# ESP_LoRa_ScaleSansotta.net
KiCad netlist of a schematic drawn in EAGLE
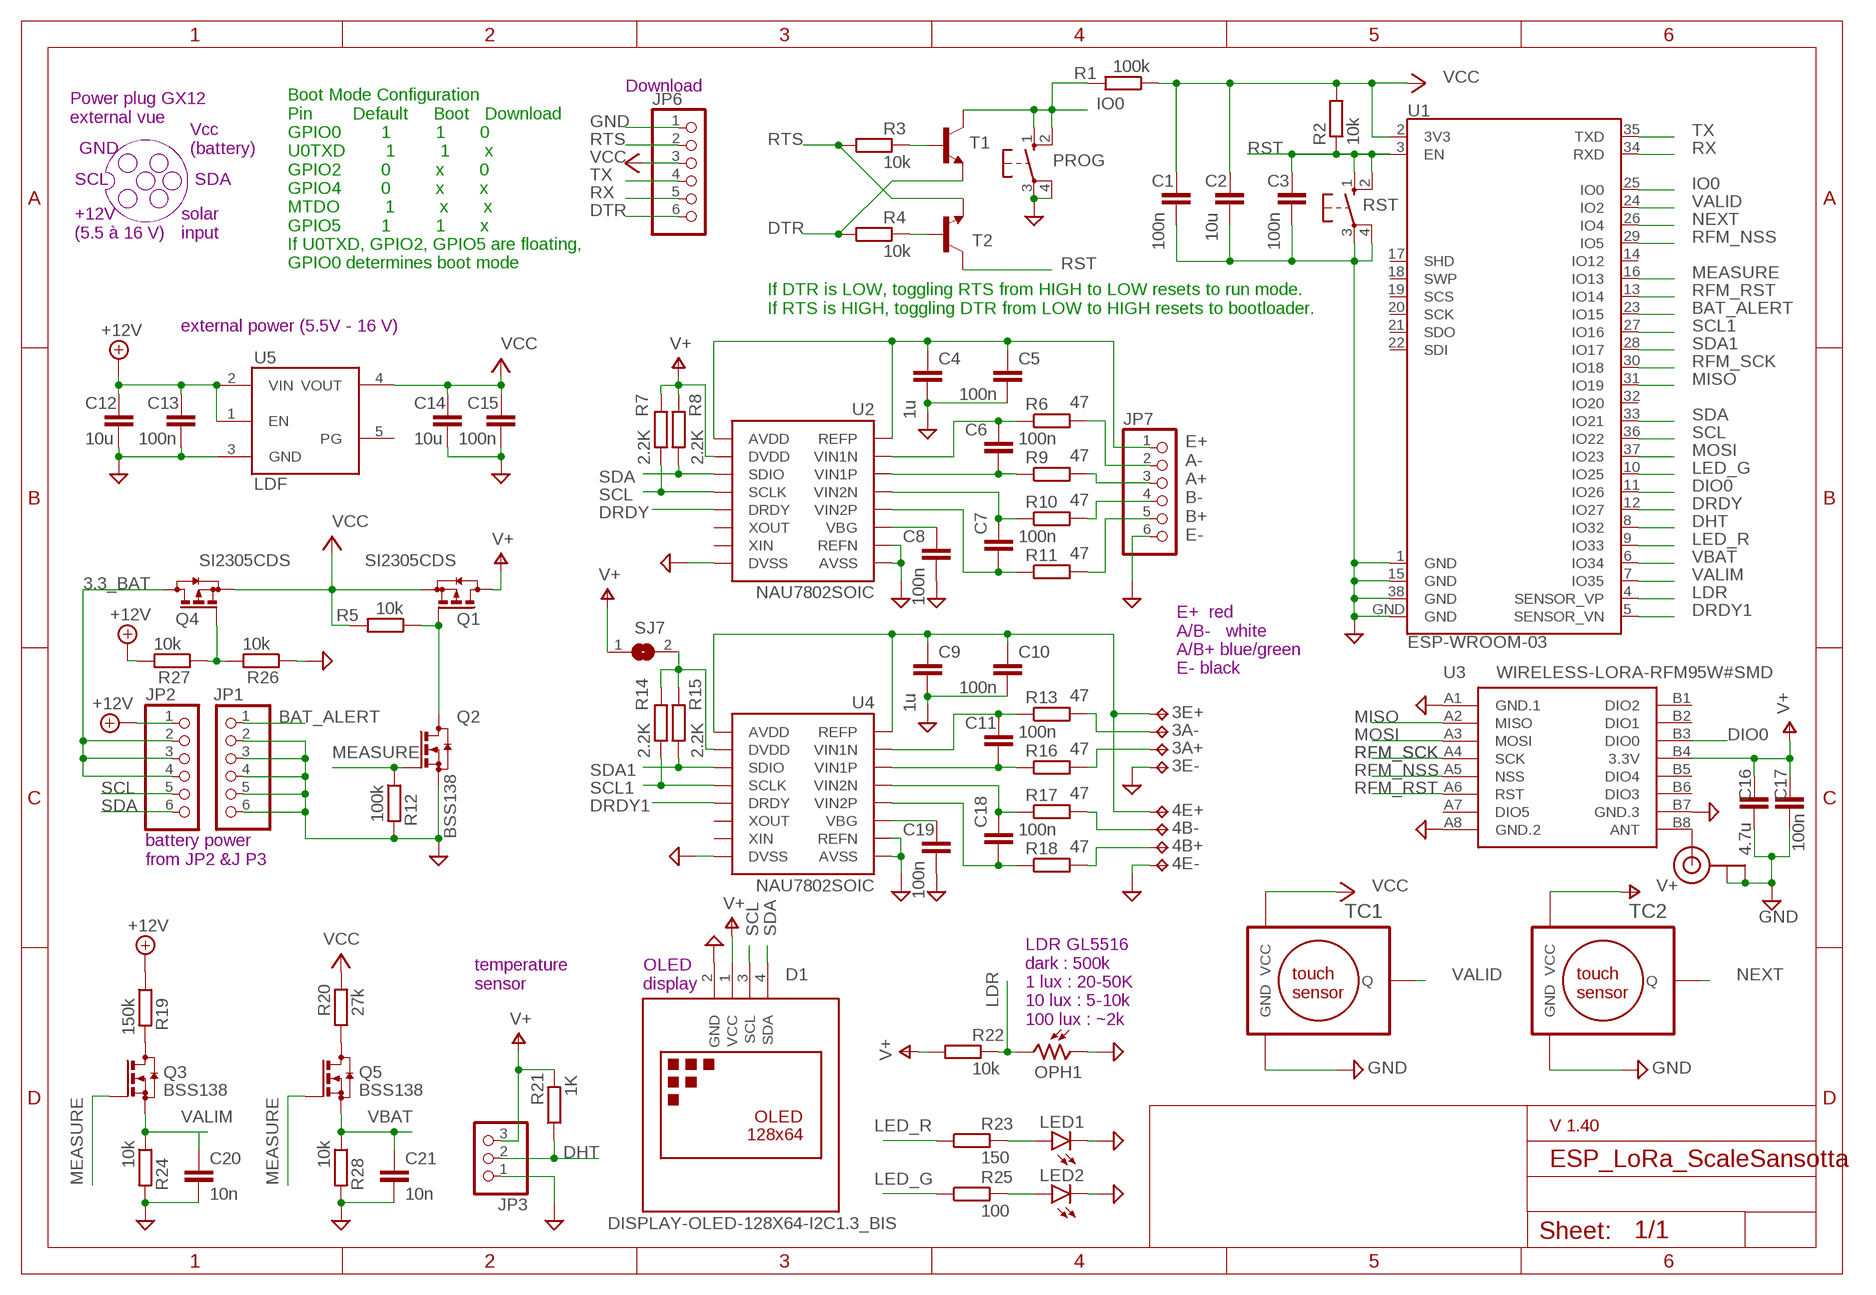
[diagram p0: schematic, sheet 1]

(export (version "E")
  (design (tool "Eeschema 10.0.6"))
  (components
    (comp (ref "3A+")
      (value "TPTP17SQ")
      (footprint "eagle-import:TP17SQ")
      (libsource (lib "eagle-import") (part "TPTP17SQ"))
    )
    (comp (ref "3A-")
      (value "TPTP17SQ")
      (footprint "eagle-import:TP17SQ")
      (libsource (lib "eagle-import") (part "TPTP17SQ"))
    )
    (comp (ref "3E+")
      (value "TPTP17SQ")
      (footprint "eagle-import:TP17SQ")
      (libsource (lib "eagle-import") (part "TPTP17SQ"))
    )
    (comp (ref "3E-")
      (value "TPTP17SQ")
      (footprint "eagle-import:TP17SQ")
      (libsource (lib "eagle-import") (part "TPTP17SQ"))
    )
    (comp (ref "4B+")
      (value "TPTP17SQ")
      (footprint "eagle-import:TP17SQ")
      (libsource (lib "eagle-import") (part "TPTP17SQ"))
    )
    (comp (ref "4B-")
      (value "TPTP17SQ")
      (footprint "eagle-import:TP17SQ")
      (libsource (lib "eagle-import") (part "TPTP17SQ"))
    )
    (comp (ref "4E+")
      (value "TPTP17SQ")
      (footprint "eagle-import:TP17SQ")
      (libsource (lib "eagle-import") (part "TPTP17SQ"))
    )
    (comp (ref "4E-")
      (value "TPTP17SQ")
      (footprint "eagle-import:TP17SQ")
      (libsource (lib "eagle-import") (part "TPTP17SQ"))
    )
    (comp (ref "C1")
      (value "100n")
      (footprint "eagle-import:C1206")
      (libsource (lib "eagle-import") (part "CC1206"))
    )
    (comp (ref "C2")
      (value "10u")
      (footprint "eagle-import:C1210")
      (libsource (lib "eagle-import") (part "CC1210"))
    )
    (comp (ref "C3")
      (value "100n")
      (footprint "eagle-import:C1206")
      (libsource (lib "eagle-import") (part "CC1206"))
    )
    (comp (ref "C4")
      (value "1u")
      (footprint "eagle-import:C1210")
      (libsource (lib "eagle-import") (part "CC1210"))
    )
    (comp (ref "C5")
      (value "100n")
      (footprint "eagle-import:C1206")
      (libsource (lib "eagle-import") (part "CC1206"))
    )
    (comp (ref "C6")
      (value "100n")
      (footprint "eagle-import:C1206")
      (libsource (lib "eagle-import") (part "CC1206"))
    )
    (comp (ref "C7")
      (value "100n")
      (footprint "eagle-import:C1206")
      (libsource (lib "eagle-import") (part "CC1206"))
    )
    (comp (ref "C8")
      (value "100n")
      (footprint "eagle-import:C1206")
      (libsource (lib "eagle-import") (part "CC1206"))
    )
    (comp (ref "C9")
      (value "1u")
      (footprint "eagle-import:C1210")
      (libsource (lib "eagle-import") (part "CC1210"))
    )
    (comp (ref "C10")
      (value "100n")
      (footprint "eagle-import:C1206")
      (libsource (lib "eagle-import") (part "CC1206"))
    )
    (comp (ref "C11")
      (value "100n")
      (footprint "eagle-import:C1206")
      (libsource (lib "eagle-import") (part "CC1206"))
    )
    (comp (ref "C12")
      (value "10u")
      (footprint "eagle-import:C1210")
      (libsource (lib "eagle-import") (part "CC1210"))
    )
    (comp (ref "C13")
      (value "100n")
      (footprint "eagle-import:C1206")
      (libsource (lib "eagle-import") (part "CC1206"))
    )
    (comp (ref "C14")
      (value "10u")
      (footprint "eagle-import:C1210")
      (libsource (lib "eagle-import") (part "CC1210"))
    )
    (comp (ref "C15")
      (value "100n")
      (footprint "eagle-import:C1206")
      (libsource (lib "eagle-import") (part "CC1206"))
    )
    (comp (ref "C16")
      (value "4.7u")
      (footprint "eagle-import:C1210")
      (libsource (lib "eagle-import") (part "CC1210"))
    )
    (comp (ref "C17")
      (value "100n")
      (footprint "eagle-import:C1206")
      (libsource (lib "eagle-import") (part "CC1206"))
    )
    (comp (ref "C18")
      (value "100n")
      (footprint "eagle-import:C1206")
      (libsource (lib "eagle-import") (part "CC1206"))
    )
    (comp (ref "C19")
      (value "100n")
      (footprint "eagle-import:C1206")
      (libsource (lib "eagle-import") (part "CC1206"))
    )
    (comp (ref "C20")
      (value "10n")
      (footprint "eagle-import:C1206")
      (libsource (lib "eagle-import") (part "CC1206"))
    )
    (comp (ref "C21")
      (value "10n")
      (footprint "eagle-import:C1206")
      (libsource (lib "eagle-import") (part "CC1206"))
    )
    (comp (ref "D1")
      (value "DISPLAY-OLED-128X64-I2C1.3_BIS")
      (footprint "eagle-import:DISPLAY-OLED-128X64-1.3-I2C_BIS")
      (libsource (lib "eagle-import") (part "DISPLAY-OLED-128X64-I2C1.3_BIS"))
    )
    (comp (ref "J1")
      (value "U.FL")
      (footprint "eagle-import:U.FL")
      (libsource (lib "eagle-import") (part "U.FL"))
    )
    (comp (ref "JP1")
      (value "PINHD-1X6")
      (footprint "eagle-import:1X06")
      (libsource (lib "eagle-import") (part "PINHD-1X6"))
    )
    (comp (ref "JP2")
      (value "PINHD-1X6")
      (footprint "eagle-import:1X06")
      (libsource (lib "eagle-import") (part "PINHD-1X6"))
    )
    (comp (ref "JP3")
      (value "PINHD-1X3")
      (footprint "eagle-import:1X03")
      (libsource (lib "eagle-import") (part "PINHD-1X3"))
    )
    (comp (ref "JP6")
      (value "PINHD-1X6")
      (footprint "eagle-import:1X06")
      (libsource (lib "eagle-import") (part "PINHD-1X6"))
    )
    (comp (ref "JP7")
      (value "PINHD-1X6")
      (footprint "eagle-import:1X06")
      (libsource (lib "eagle-import") (part "PINHD-1X6"))
    )
    (comp (ref "LED1")
      (value "LEDSMT1206")
      (footprint "eagle-import:1206")
      (libsource (lib "eagle-import") (part "LEDSMT1206"))
    )
    (comp (ref "LED2")
      (value "LEDSMT1206")
      (footprint "eagle-import:1206")
      (libsource (lib "eagle-import") (part "LEDSMT1206"))
    )
    (comp (ref "OPH1")
      (value "VT93N2")
      (footprint "eagle-import:VT900")
      (libsource (lib "eagle-import") (part "VT93N2"))
    )
    (comp (ref "PROG")
      (value "10-XX")
      (footprint "eagle-import:B3F-10XX")
      (fields (field (name "MPN") "B3F-1000"))
      (libsource (lib "eagle-import") (part "10-XX"))
    )
    (comp (ref "Q1")
      (value "SI2305CDS")
      (footprint "eagle-import:SOT23")
      (libsource (lib "eagle-import") (part "SI2305CDS"))
    )
    (comp (ref "Q2")
      (value "BSS138")
      (footprint "eagle-import:SOT23")
      (libsource (lib "eagle-import") (part "BSS138"))
    )
    (comp (ref "Q3")
      (value "BSS138")
      (footprint "eagle-import:SOT23")
      (libsource (lib "eagle-import") (part "BSS138"))
    )
    (comp (ref "Q4")
      (value "SI2305CDS")
      (footprint "eagle-import:SOT23")
      (libsource (lib "eagle-import") (part "SI2305CDS"))
    )
    (comp (ref "Q5")
      (value "BSS138")
      (footprint "eagle-import:SOT23")
      (libsource (lib "eagle-import") (part "BSS138"))
    )
    (comp (ref "R1")
      (value "100k")
      (footprint "eagle-import:R1206")
      (libsource (lib "eagle-import") (part "RR1206"))
    )
    (comp (ref "R2")
      (value "10k")
      (footprint "eagle-import:R1206")
      (libsource (lib "eagle-import") (part "RR1206"))
    )
    (comp (ref "R3")
      (value "10k")
      (footprint "eagle-import:R1206")
      (libsource (lib "eagle-import") (part "RR1206"))
    )
    (comp (ref "R4")
      (value "10k")
      (footprint "eagle-import:R1206")
      (libsource (lib "eagle-import") (part "RR1206"))
    )
    (comp (ref "R5")
      (value "10k")
      (footprint "eagle-import:R1206")
      (libsource (lib "eagle-import") (part "RR1206"))
    )
    (comp (ref "R6")
      (value "47")
      (footprint "eagle-import:R1206")
      (libsource (lib "eagle-import") (part "RR1206"))
    )
    (comp (ref "R7")
      (value "2.2K")
      (footprint "eagle-import:R1206")
      (libsource (lib "eagle-import") (part "RR1206"))
    )
    (comp (ref "R8")
      (value "2.2K")
      (footprint "eagle-import:R1206")
      (libsource (lib "eagle-import") (part "RR1206"))
    )
    (comp (ref "R9")
      (value "47")
      (footprint "eagle-import:R1206")
      (libsource (lib "eagle-import") (part "RR1206"))
    )
    (comp (ref "R10")
      (value "47")
      (footprint "eagle-import:R1206")
      (libsource (lib "eagle-import") (part "RR1206"))
    )
    (comp (ref "R11")
      (value "47")
      (footprint "eagle-import:R1206")
      (libsource (lib "eagle-import") (part "RR1206"))
    )
    (comp (ref "R12")
      (value "100k")
      (footprint "eagle-import:R1206")
      (libsource (lib "eagle-import") (part "RR1206"))
    )
    (comp (ref "R13")
      (value "47")
      (footprint "eagle-import:R1206")
      (libsource (lib "eagle-import") (part "RR1206"))
    )
    (comp (ref "R14")
      (value "2.2K")
      (footprint "eagle-import:R1206")
      (libsource (lib "eagle-import") (part "RR1206"))
    )
    (comp (ref "R15")
      (value "2.2K")
      (footprint "eagle-import:R1206")
      (libsource (lib "eagle-import") (part "RR1206"))
    )
    (comp (ref "R16")
      (value "47")
      (footprint "eagle-import:R1206")
      (libsource (lib "eagle-import") (part "RR1206"))
    )
    (comp (ref "R17")
      (value "47")
      (footprint "eagle-import:R1206")
      (libsource (lib "eagle-import") (part "RR1206"))
    )
    (comp (ref "R18")
      (value "47")
      (footprint "eagle-import:R1206")
      (libsource (lib "eagle-import") (part "RR1206"))
    )
    (comp (ref "R19")
      (value "150k")
      (footprint "eagle-import:R1206")
      (libsource (lib "eagle-import") (part "RR1206"))
    )
    (comp (ref "R20")
      (value "27k")
      (footprint "eagle-import:R1206")
      (libsource (lib "eagle-import") (part "RR1206"))
    )
    (comp (ref "R21")
      (value "1K")
      (footprint "eagle-import:R1206")
      (libsource (lib "eagle-import") (part "RR1206"))
    )
    (comp (ref "R22")
      (value "10k")
      (footprint "eagle-import:R1206")
      (libsource (lib "eagle-import") (part "RR1206"))
    )
    (comp (ref "R23")
      (value "150")
      (footprint "eagle-import:R1206")
      (libsource (lib "eagle-import") (part "RR1206"))
    )
    (comp (ref "R24")
      (value "10k")
      (footprint "eagle-import:R1206")
      (libsource (lib "eagle-import") (part "RR1206"))
    )
    (comp (ref "R25")
      (value "100")
      (footprint "eagle-import:R1206")
      (libsource (lib "eagle-import") (part "RR1206"))
    )
    (comp (ref "R26")
      (value "10k")
      (footprint "eagle-import:R1206")
      (libsource (lib "eagle-import") (part "RR1206"))
    )
    (comp (ref "R27")
      (value "10k")
      (footprint "eagle-import:R1206")
      (libsource (lib "eagle-import") (part "RR1206"))
    )
    (comp (ref "R28")
      (value "10k")
      (footprint "eagle-import:R1206")
      (libsource (lib "eagle-import") (part "RR1206"))
    )
    (comp (ref "RST")
      (value "10-XX")
      (footprint "eagle-import:B3F-10XX")
      (fields (field (name "MPN") "B3F-1000"))
      (libsource (lib "eagle-import") (part "10-XX"))
    )
    (comp (ref "SJ7") (value "SJ") (footprint "eagle-import:SJ") (libsource (lib "eagle-import") (part "SJ")))
    (comp (ref "T1")
      (value "MMBT2222ALT1-NPN-SOT23-BEC")
      (footprint "eagle-import:SOT23-BEC")
      (libsource (lib "eagle-import") (part "-NPN-SOT23-BECMMBT2222ALT1"))
    )
    (comp (ref "T2")
      (value "MMBT2222ALT1-NPN-SOT23-BEC")
      (footprint "eagle-import:SOT23-BEC")
      (libsource (lib "eagle-import") (part "-NPN-SOT23-BECMMBT2222ALT1"))
    )
    (comp (ref "TC1")
      (value "TTP223R_H")
      (footprint "eagle-import:TTP233RED_H")
      (libsource (lib "eagle-import") (part "TTP223R_H"))
    )
    (comp (ref "TC2")
      (value "TTP223R_H")
      (footprint "eagle-import:TTP233RED_H")
      (libsource (lib "eagle-import") (part "TTP223R_H"))
    )
    (comp (ref "U1")
      (value "ESP-WROOM-03")
      (footprint "eagle-import:ESP-WROOM-03")
      (libsource (lib "eagle-import") (part "ESP-WROOM-03"))
    )
    (comp (ref "U2")
      (value "NAU7802SOIC")
      (footprint "eagle-import:SO16")
      (libsource (lib "eagle-import") (part "NAU7802SOIC"))
    )
    (comp (ref "U3")
      (value "WIRELESS-LORA-RFM95W#SMD")
      (footprint "eagle-import:WIRELESS-LORA-RFM95W#SMD")
      (libsource (lib "eagle-import") (part "WIRELESS-LORA-RFM95W#SMD"))
    )
    (comp (ref "U4")
      (value "NAU7802SOIC")
      (footprint "eagle-import:SO16")
      (libsource (lib "eagle-import") (part "NAU7802SOIC"))
    )
    (comp (ref "U5")
      (value "LDF3.3")
      (footprint "eagle-import:PPAK")
      (libsource (lib "eagle-import") (part "LDF3.3"))
    )
  )
  (nets
    (net (code "1") (name "+12V") (class "Default")
      (node (ref "C12") (pin "1") (pinfunction "1_1") (pintype "passive"))
      (node (ref "C13") (pin "1") (pinfunction "1_1") (pintype "passive"))
      (node (ref "JP2") (pin "1") (pinfunction "1_1") (pintype "passive"))
      (node (ref "R19") (pin "1") (pinfunction "1_1") (pintype "passive"))
      (node (ref "R27") (pin "2") (pinfunction "2_2") (pintype "passive"))
      (node (ref "U5") (pin "1") (pinfunction "EN_1") (pintype "input"))
      (node (ref "U5") (pin "2") (pinfunction "VIN_2") (pintype "power_in"))
    )
    (net (code "2") (name "/3.3_BAT") (class "Default")
      (node (ref "JP2") (pin "2") (pinfunction "2_2") (pintype "passive"))
      (node (ref "JP2") (pin "3") (pinfunction "3_3") (pintype "passive"))
      (node (ref "JP2") (pin "4") (pinfunction "4_4") (pintype "passive"))
      (node (ref "Q4") (pin "3") (pinfunction "D_3") (pintype "passive"))
    )
    (net (code "3") (name "/BAT_ALERT") (class "Default")
      (node (ref "JP1") (pin "1") (pinfunction "1_1") (pintype "passive"))
      (node (ref "U1") (pin "23") (pinfunction "IO15_23") (pintype "bidirectional"))
    )
    (net (code "4") (name "/DHT") (class "Default")
      (node (ref "JP3") (pin "2") (pinfunction "2_2") (pintype "passive"))
      (node (ref "R21") (pin "1") (pinfunction "1_1") (pintype "passive"))
      (node (ref "U1") (pin "8") (pinfunction "IO32_8") (pintype "bidirectional"))
    )
    (net (code "5") (name "/DIO0") (class "Default")
      (node (ref "U1") (pin "11") (pinfunction "IO26_11") (pintype "bidirectional"))
      (node (ref "U3") (pin "B3") (pinfunction "DIO0_B3") (pintype "bidirectional"))
    )
    (net (code "6") (name "/DRDY") (class "Default")
      (node (ref "U1") (pin "12") (pinfunction "IO27_12") (pintype "bidirectional"))
      (node (ref "U2") (pin "12") (pinfunction "DRDY_12") (pintype "bidirectional"))
    )
    (net (code "7") (name "/DRDY1") (class "Default")
      (node (ref "U1") (pin "5") (pinfunction "SENSOR_VN_5") (pintype "bidirectional"))
      (node (ref "U4") (pin "12") (pinfunction "DRDY_12") (pintype "bidirectional"))
    )
    (net (code "8") (name "/DTR") (class "Default")
      (node (ref "JP6") (pin "6") (pinfunction "6_6") (pintype "passive"))
      (node (ref "R4") (pin "1") (pinfunction "1_1") (pintype "passive"))
      (node (ref "T1") (pin "E") (pinfunction "E_E") (pintype "passive"))
    )
    (net (code "9") (name "/IO0") (class "Default")
      (node (ref "PROG") (pin "1") (pinfunction "S_1") (pintype "passive"))
      (node (ref "PROG") (pin "2") (pinfunction "S1_2") (pintype "passive"))
      (node (ref "R1") (pin "2") (pinfunction "2_2") (pintype "passive"))
      (node (ref "T1") (pin "C") (pinfunction "C_C") (pintype "passive"))
      (node (ref "U1") (pin "25") (pinfunction "IO0_25") (pintype "bidirectional"))
    )
    (net (code "10") (name "/LDR") (class "Default")
      (node (ref "OPH1") (pin "2") (pinfunction "2_2") (pintype "passive"))
      (node (ref "R22") (pin "2") (pinfunction "2_2") (pintype "passive"))
      (node (ref "U1") (pin "4") (pinfunction "SENSOR_VP_4") (pintype "bidirectional"))
    )
    (net (code "11") (name "/LED_G") (class "Default")
      (node (ref "R25") (pin "1") (pinfunction "1_1") (pintype "passive"))
      (node (ref "U1") (pin "10") (pinfunction "IO25_10") (pintype "bidirectional"))
    )
    (net (code "12") (name "/LED_R") (class "Default")
      (node (ref "R23") (pin "1") (pinfunction "1_1") (pintype "passive"))
      (node (ref "U1") (pin "9") (pinfunction "IO33_9") (pintype "bidirectional"))
    )
    (net (code "13") (name "/MEASURE") (class "Default")
      (node (ref "Q2") (pin "1") (pinfunction "G_1") (pintype "passive"))
      (node (ref "Q3") (pin "1") (pinfunction "G_1") (pintype "passive"))
      (node (ref "Q5") (pin "1") (pinfunction "G_1") (pintype "passive"))
      (node (ref "R12") (pin "1") (pinfunction "1_1") (pintype "passive"))
      (node (ref "U1") (pin "16") (pinfunction "IO13_16") (pintype "bidirectional"))
    )
    (net (code "14") (name "/MISO") (class "Default")
      (node (ref "U1") (pin "31") (pinfunction "IO19_31") (pintype "bidirectional"))
      (node (ref "U3") (pin "A2") (pinfunction "MISO_A2") (pintype "bidirectional"))
    )
    (net (code "15") (name "/MOSI") (class "Default")
      (node (ref "U1") (pin "37") (pinfunction "IO23_37") (pintype "bidirectional"))
      (node (ref "U3") (pin "A3") (pinfunction "MOSI_A3") (pintype "bidirectional"))
    )
    (net (code "16") (name "/NEXT") (class "Default")
      (node (ref "TC2") (pin "P$2") (pinfunction "Q_P$2") (pintype "power_in"))
      (node (ref "U1") (pin "26") (pinfunction "IO4_26") (pintype "bidirectional"))
    )
    (net (code "17") (name "/PG") (class "Default")
      (node (ref "U5") (pin "5") (pinfunction "PG_5") (pintype "power_in"))
    )
    (net (code "18") (name "/RFM_NSS") (class "Default")
      (node (ref "U1") (pin "29") (pinfunction "IO5_29") (pintype "bidirectional"))
      (node (ref "U3") (pin "A5") (pinfunction "NSS_A5") (pintype "bidirectional"))
    )
    (net (code "19") (name "/RFM_RST") (class "Default")
      (node (ref "U1") (pin "13") (pinfunction "IO14_13") (pintype "bidirectional"))
      (node (ref "U3") (pin "A6") (pinfunction "RST_A6") (pintype "bidirectional"))
    )
    (net (code "20") (name "/RFM_SCK") (class "Default")
      (node (ref "U1") (pin "30") (pinfunction "IO18_30") (pintype "bidirectional"))
      (node (ref "U3") (pin "A4") (pinfunction "SCK_A4") (pintype "bidirectional"))
    )
    (net (code "21") (name "/RST") (class "Default")
      (node (ref "C3") (pin "1") (pinfunction "1_1") (pintype "passive"))
      (node (ref "R2") (pin "1") (pinfunction "1_1") (pintype "passive"))
      (node (ref "RST") (pin "1") (pinfunction "S_1") (pintype "passive"))
      (node (ref "RST") (pin "2") (pinfunction "S1_2") (pintype "passive"))
      (node (ref "T2") (pin "C") (pinfunction "C_C") (pintype "passive"))
      (node (ref "U1") (pin "3") (pinfunction "EN_3") (pintype "bidirectional"))
    )
    (net (code "22") (name "/RTS") (class "Default")
      (node (ref "JP6") (pin "2") (pinfunction "2_2") (pintype "passive"))
      (node (ref "R3") (pin "1") (pinfunction "1_1") (pintype "passive"))
      (node (ref "T2") (pin "E") (pinfunction "E_E") (pintype "passive"))
    )
    (net (code "23") (name "/RX") (class "Default")
      (node (ref "JP6") (pin "5") (pinfunction "5_5") (pintype "passive"))
      (node (ref "U1") (pin "34") (pinfunction "RXD_34") (pintype "bidirectional"))
    )
    (net (code "24") (name "/SCL") (class "Default")
      (node (ref "D1") (pin "3") (pinfunction "SCL_3") (pintype "bidirectional"))
      (node (ref "JP2") (pin "5") (pinfunction "5_5") (pintype "passive"))
      (node (ref "R7") (pin "1") (pinfunction "1_1") (pintype "passive"))
      (node (ref "U1") (pin "36") (pinfunction "IO22_36") (pintype "bidirectional"))
      (node (ref "U2") (pin "13") (pinfunction "SCLK_13") (pintype "bidirectional"))
    )
    (net (code "25") (name "/SCL1") (class "Default")
      (node (ref "R14") (pin "1") (pinfunction "1_1") (pintype "passive"))
      (node (ref "U1") (pin "27") (pinfunction "IO16_27") (pintype "bidirectional"))
      (node (ref "U4") (pin "13") (pinfunction "SCLK_13") (pintype "bidirectional"))
    )
    (net (code "26") (name "/SDA") (class "Default")
      (node (ref "D1") (pin "4") (pinfunction "SDA_4") (pintype "bidirectional"))
      (node (ref "JP2") (pin "6") (pinfunction "6_6") (pintype "passive"))
      (node (ref "R8") (pin "1") (pinfunction "1_1") (pintype "passive"))
      (node (ref "U1") (pin "33") (pinfunction "IO21_33") (pintype "bidirectional"))
      (node (ref "U2") (pin "14") (pinfunction "SDIO_14") (pintype "bidirectional"))
    )
    (net (code "27") (name "/SDA1") (class "Default")
      (node (ref "R15") (pin "1") (pinfunction "1_1") (pintype "passive"))
      (node (ref "U1") (pin "28") (pinfunction "IO17_28") (pintype "bidirectional"))
      (node (ref "U4") (pin "14") (pinfunction "SDIO_14") (pintype "bidirectional"))
    )
    (net (code "28") (name "/TX") (class "Default")
      (node (ref "JP6") (pin "4") (pinfunction "4_4") (pintype "passive"))
      (node (ref "U1") (pin "35") (pinfunction "TXD_35") (pintype "bidirectional"))
    )
    (net (code "29") (name "/VALID") (class "Default")
      (node (ref "TC1") (pin "P$2") (pinfunction "Q_P$2") (pintype "power_in"))
      (node (ref "U1") (pin "24") (pinfunction "IO2_24") (pintype "bidirectional"))
    )
    (net (code "30") (name "/VALIM") (class "Default")
      (node (ref "C20") (pin "1") (pinfunction "1_1") (pintype "passive"))
      (node (ref "Q3") (pin "2") (pinfunction "S_2") (pintype "passive"))
      (node (ref "R24") (pin "1") (pinfunction "1_1") (pintype "passive"))
      (node (ref "U1") (pin "7") (pinfunction "IO35_7") (pintype "bidirectional"))
    )
    (net (code "31") (name "/VBAT") (class "Default")
      (node (ref "C21") (pin "1") (pinfunction "1_1") (pintype "passive"))
      (node (ref "Q5") (pin "2") (pinfunction "S_2") (pintype "passive"))
      (node (ref "R28") (pin "1") (pinfunction "1_1") (pintype "passive"))
      (node (ref "U1") (pin "6") (pinfunction "IO34_6") (pintype "bidirectional"))
    )
    (net (code "32") (name "GND") (class "Default")
      (node (ref "3E-") (pin "TP") (pinfunction "TP_TP") (pintype "input"))
      (node (ref "4E-") (pin "TP") (pinfunction "TP_TP") (pintype "input"))
      (node (ref "C1") (pin "2") (pinfunction "2_2") (pintype "passive"))
      (node (ref "C10") (pin "2") (pinfunction "2_2") (pintype "passive"))
      (node (ref "C12") (pin "2") (pinfunction "2_2") (pintype "passive"))
      (node (ref "C13") (pin "2") (pinfunction "2_2") (pintype "passive"))
      (node (ref "C14") (pin "2") (pinfunction "2_2") (pintype "passive"))
      (node (ref "C15") (pin "2") (pinfunction "2_2") (pintype "passive"))
      (node (ref "C16") (pin "2") (pinfunction "2_2") (pintype "passive"))
      (node (ref "C17") (pin "2") (pinfunction "2_2") (pintype "passive"))
      (node (ref "C19") (pin "2") (pinfunction "2_2") (pintype "passive"))
      (node (ref "C2") (pin "2") (pinfunction "2_2") (pintype "passive"))
      (node (ref "C20") (pin "2") (pinfunction "2_2") (pintype "passive"))
      (node (ref "C21") (pin "2") (pinfunction "2_2") (pintype "passive"))
      (node (ref "C3") (pin "2") (pinfunction "2_2") (pintype "passive"))
      (node (ref "C4") (pin "2") (pinfunction "2_2") (pintype "passive"))
      (node (ref "C5") (pin "2") (pinfunction "2_2") (pintype "passive"))
      (node (ref "C8") (pin "2") (pinfunction "2_2") (pintype "passive"))
      (node (ref "C9") (pin "2") (pinfunction "2_2") (pintype "passive"))
      (node (ref "D1") (pin "2") (pinfunction "GND_2") (pintype "power_in"))
      (node (ref "J1") (pin "1") (pinfunction "GND_1") (pintype "passive"))
      (node (ref "J1") (pin "2") (pinfunction "GND_2") (pintype "passive"))
      (node (ref "JP1") (pin "2") (pinfunction "2_2") (pintype "passive"))
      (node (ref "JP1") (pin "3") (pinfunction "3_3") (pintype "passive"))
      (node (ref "JP1") (pin "4") (pinfunction "4_4") (pintype "passive"))
      (node (ref "JP1") (pin "5") (pinfunction "5_5") (pintype "passive"))
      (node (ref "JP1") (pin "6") (pinfunction "6_6") (pintype "passive"))
      (node (ref "JP3") (pin "1") (pinfunction "1_1") (pintype "passive"))
      (node (ref "JP6") (pin "1") (pinfunction "1_1") (pintype "passive"))
      (node (ref "JP7") (pin "6") (pinfunction "6_6") (pintype "passive"))
      (node (ref "LED1") (pin "C") (pinfunction "C_C") (pintype "passive"))
      (node (ref "LED2") (pin "C") (pinfunction "C_C") (pintype "passive"))
      (node (ref "OPH1") (pin "1") (pinfunction "1_1") (pintype "passive"))
      (node (ref "PROG") (pin "3") (pinfunction "P_3") (pintype "passive"))
      (node (ref "PROG") (pin "4") (pinfunction "P1_4") (pintype "passive"))
      (node (ref "Q2") (pin "2") (pinfunction "S_2") (pintype "passive"))
      (node (ref "R12") (pin "2") (pinfunction "2_2") (pintype "passive"))
      (node (ref "R24") (pin "2") (pinfunction "2_2") (pintype "passive"))
      (node (ref "R26") (pin "1") (pinfunction "1_1") (pintype "passive"))
      (node (ref "R28") (pin "2") (pinfunction "2_2") (pintype "passive"))
      (node (ref "RST") (pin "3") (pinfunction "P_3") (pintype "passive"))
      (node (ref "RST") (pin "4") (pinfunction "P1_4") (pintype "passive"))
      (node (ref "TC1") (pin "P$3") (pinfunction "GND_P$3") (pintype "power_in"))
      (node (ref "TC2") (pin "P$3") (pinfunction "GND_P$3") (pintype "power_in"))
      (node (ref "U1") (pin "1") (pinfunction "GND_1") (pintype "bidirectional"))
      (node (ref "U1") (pin "15") (pinfunction "GND_15") (pintype "bidirectional"))
      (node (ref "U1") (pin "38") (pinfunction "GND_38") (pintype "bidirectional"))
      (node (ref "U1") (pin "GND") (pinfunction "GND_GND") (pintype "bidirectional"))
      (node (ref "U2") (pin "7") (pinfunction "REFN_7") (pintype "bidirectional"))
      (node (ref "U2") (pin "8") (pinfunction "AVSS_8") (pintype "bidirectional"))
      (node (ref "U2") (pin "9") (pinfunction "DVSS_9") (pintype "bidirectional"))
      (node (ref "U3") (pin "A1") (pinfunction "GND.1_A1") (pintype "power_in"))
      (node (ref "U3") (pin "A8") (pinfunction "GND.2_A8") (pintype "power_in"))
      (node (ref "U3") (pin "B7") (pinfunction "GND.3_B7") (pintype "power_in"))
      (node (ref "U4") (pin "7") (pinfunction "REFN_7") (pintype "bidirectional"))
      (node (ref "U4") (pin "8") (pinfunction "AVSS_8") (pintype "bidirectional"))
      (node (ref "U4") (pin "9") (pinfunction "DVSS_9") (pintype "bidirectional"))
      (node (ref "U5") (pin "3") (pinfunction "GND_3") (pintype "power_in"))
    )
    (net (code "33") (name "Net-(3A+-PadTP)") (class "Default")
      (node (ref "3A+") (pin "TP") (pinfunction "TP_TP") (pintype "input"))
      (node (ref "R16") (pin "2") (pinfunction "2_2") (pintype "passive"))
    )
    (net (code "34") (name "Net-(3A--PadTP)") (class "Default")
      (node (ref "3A-") (pin "TP") (pinfunction "TP_TP") (pintype "input"))
      (node (ref "R13") (pin "2") (pinfunction "2_2") (pintype "passive"))
    )
    (net (code "35") (name "Net-(4B+-PadTP)") (class "Default")
      (node (ref "4B+") (pin "TP") (pinfunction "TP_TP") (pintype "input"))
      (node (ref "R18") (pin "2") (pinfunction "2_2") (pintype "passive"))
    )
    (net (code "36") (name "Net-(4B--PadTP)") (class "Default")
      (node (ref "4B-") (pin "TP") (pinfunction "TP_TP") (pintype "input"))
      (node (ref "R17") (pin "2") (pinfunction "2_2") (pintype "passive"))
    )
    (net (code "37") (name "Net-(J1-SIGNAL)") (class "Default")
      (node (ref "J1") (pin "3") (pinfunction "SIGNAL_3") (pintype "passive"))
      (node (ref "U3") (pin "B8") (pinfunction "ANT_B8") (pintype "passive"))
    )
    (net (code "38") (name "Net-(JP7-Pad2)") (class "Default")
      (node (ref "JP7") (pin "2") (pinfunction "2_2") (pintype "passive"))
      (node (ref "R6") (pin "2") (pinfunction "2_2") (pintype "passive"))
    )
    (net (code "39") (name "Net-(JP7-Pad3)") (class "Default")
      (node (ref "JP7") (pin "3") (pinfunction "3_3") (pintype "passive"))
      (node (ref "R9") (pin "2") (pinfunction "2_2") (pintype "passive"))
    )
    (net (code "40") (name "Net-(JP7-Pad4)") (class "Default")
      (node (ref "JP7") (pin "4") (pinfunction "4_4") (pintype "passive"))
      (node (ref "R10") (pin "2") (pinfunction "2_2") (pintype "passive"))
    )
    (net (code "41") (name "Net-(JP7-Pad5)") (class "Default")
      (node (ref "JP7") (pin "5") (pinfunction "5_5") (pintype "passive"))
      (node (ref "R11") (pin "2") (pinfunction "2_2") (pintype "passive"))
    )
    (net (code "42") (name "Net-(LED1-PadA)") (class "Default")
      (node (ref "LED1") (pin "A") (pinfunction "A_A") (pintype "passive"))
      (node (ref "R23") (pin "2") (pinfunction "2_2") (pintype "passive"))
    )
    (net (code "43") (name "Net-(LED2-PadA)") (class "Default")
      (node (ref "LED2") (pin "A") (pinfunction "A_A") (pintype "passive"))
      (node (ref "R25") (pin "2") (pinfunction "2_2") (pintype "passive"))
    )
    (net (code "44") (name "Net-(Q1-G)") (class "Default")
      (node (ref "Q1") (pin "1") (pinfunction "G_1") (pintype "passive"))
      (node (ref "Q2") (pin "3") (pinfunction "D_3") (pintype "passive"))
      (node (ref "R5") (pin "1") (pinfunction "1_1") (pintype "passive"))
    )
    (net (code "45") (name "Net-(Q3-D)") (class "Default")
      (node (ref "Q3") (pin "3") (pinfunction "D_3") (pintype "passive"))
      (node (ref "R19") (pin "2") (pinfunction "2_2") (pintype "passive"))
    )
    (net (code "46") (name "Net-(Q4-G)") (class "Default")
      (node (ref "Q4") (pin "1") (pinfunction "G_1") (pintype "passive"))
      (node (ref "R26") (pin "2") (pinfunction "2_2") (pintype "passive"))
      (node (ref "R27") (pin "1") (pinfunction "1_1") (pintype "passive"))
    )
    (net (code "47") (name "Net-(Q5-D)") (class "Default")
      (node (ref "Q5") (pin "3") (pinfunction "D_3") (pintype "passive"))
      (node (ref "R20") (pin "1") (pinfunction "1_1") (pintype "passive"))
    )
    (net (code "48") (name "Net-(R3-Pad2)") (class "Default")
      (node (ref "R3") (pin "2") (pinfunction "2_2") (pintype "passive"))
      (node (ref "T1") (pin "B") (pinfunction "B_B") (pintype "passive"))
    )
    (net (code "49") (name "Net-(R4-Pad2)") (class "Default")
      (node (ref "R4") (pin "2") (pinfunction "2_2") (pintype "passive"))
      (node (ref "T2") (pin "B") (pinfunction "B_B") (pintype "passive"))
    )
    (net (code "50") (name "Net-(U2-AVDD)") (class "Default")
      (node (ref "C4") (pin "1") (pinfunction "1_1") (pintype "passive"))
      (node (ref "C5") (pin "1") (pinfunction "1_1") (pintype "passive"))
      (node (ref "JP7") (pin "1") (pinfunction "1_1") (pintype "passive"))
      (node (ref "U2") (pin "1") (pinfunction "REFP_1") (pintype "bidirectional"))
      (node (ref "U2") (pin "16") (pinfunction "AVDD_16") (pintype "bidirectional"))
    )
    (net (code "51") (name "Net-(U2-VBG)") (class "Default")
      (node (ref "C8") (pin "1") (pinfunction "1_1") (pintype "passive"))
      (node (ref "U2") (pin "6") (pinfunction "VBG_6") (pintype "bidirectional"))
    )
    (net (code "52") (name "Net-(U2-VIN1N)") (class "Default")
      (node (ref "C6") (pin "1") (pinfunction "1_1") (pintype "passive"))
      (node (ref "R6") (pin "1") (pinfunction "1_1") (pintype "passive"))
      (node (ref "U2") (pin "2") (pinfunction "VIN1N_2") (pintype "bidirectional"))
    )
    (net (code "53") (name "Net-(U2-VIN1P)") (class "Default")
      (node (ref "C6") (pin "2") (pinfunction "2_2") (pintype "passive"))
      (node (ref "R9") (pin "1") (pinfunction "1_1") (pintype "passive"))
      (node (ref "U2") (pin "3") (pinfunction "VIN1P_3") (pintype "bidirectional"))
    )
    (net (code "54") (name "Net-(U2-VIN2N)") (class "Default")
      (node (ref "C7") (pin "1") (pinfunction "1_1") (pintype "passive"))
      (node (ref "R10") (pin "1") (pinfunction "1_1") (pintype "passive"))
      (node (ref "U2") (pin "4") (pinfunction "VIN2N_4") (pintype "bidirectional"))
    )
    (net (code "55") (name "Net-(U2-VIN2P)") (class "Default")
      (node (ref "C7") (pin "2") (pinfunction "2_2") (pintype "passive"))
      (node (ref "R11") (pin "1") (pinfunction "1_1") (pintype "passive"))
      (node (ref "U2") (pin "5") (pinfunction "VIN2P_5") (pintype "bidirectional"))
    )
    (net (code "56") (name "Net-(U4-AVDD)") (class "Default")
      (node (ref "3E+") (pin "TP") (pinfunction "TP_TP") (pintype "input"))
      (node (ref "4E+") (pin "TP") (pinfunction "TP_TP") (pintype "input"))
      (node (ref "C10") (pin "1") (pinfunction "1_1") (pintype "passive"))
      (node (ref "C9") (pin "1") (pinfunction "1_1") (pintype "passive"))
      (node (ref "U4") (pin "1") (pinfunction "REFP_1") (pintype "bidirectional"))
      (node (ref "U4") (pin "16") (pinfunction "AVDD_16") (pintype "bidirectional"))
    )
    (net (code "57") (name "Net-(U4-DVDD)") (class "Default")
      (node (ref "R14") (pin "2") (pinfunction "2_2") (pintype "passive"))
      (node (ref "R15") (pin "2") (pinfunction "2_2") (pintype "passive"))
      (node (ref "SJ7") (pin "2") (pinfunction "2_2") (pintype "passive"))
      (node (ref "U4") (pin "15") (pinfunction "DVDD_15") (pintype "bidirectional"))
    )
    (net (code "58") (name "Net-(U4-VBG)") (class "Default")
      (node (ref "C19") (pin "1") (pinfunction "1_1") (pintype "passive"))
      (node (ref "U4") (pin "6") (pinfunction "VBG_6") (pintype "bidirectional"))
    )
    (net (code "59") (name "Net-(U4-VIN1N)") (class "Default")
      (node (ref "C11") (pin "1") (pinfunction "1_1") (pintype "passive"))
      (node (ref "R13") (pin "1") (pinfunction "1_1") (pintype "passive"))
      (node (ref "U4") (pin "2") (pinfunction "VIN1N_2") (pintype "bidirectional"))
    )
    (net (code "60") (name "Net-(U4-VIN1P)") (class "Default")
      (node (ref "C11") (pin "2") (pinfunction "2_2") (pintype "passive"))
      (node (ref "R16") (pin "1") (pinfunction "1_1") (pintype "passive"))
      (node (ref "U4") (pin "3") (pinfunction "VIN1P_3") (pintype "bidirectional"))
    )
    (net (code "61") (name "Net-(U4-VIN2N)") (class "Default")
      (node (ref "C18") (pin "1") (pinfunction "1_1") (pintype "passive"))
      (node (ref "R17") (pin "1") (pinfunction "1_1") (pintype "passive"))
      (node (ref "U4") (pin "4") (pinfunction "VIN2N_4") (pintype "bidirectional"))
    )
    (net (code "62") (name "Net-(U4-VIN2P)") (class "Default")
      (node (ref "C18") (pin "2") (pinfunction "2_2") (pintype "passive"))
      (node (ref "R18") (pin "1") (pinfunction "1_1") (pintype "passive"))
      (node (ref "U4") (pin "5") (pinfunction "VIN2P_5") (pintype "bidirectional"))
    )
    (net (code "63") (name "V+") (class "Default")
      (node (ref "C16") (pin "1") (pinfunction "1_1") (pintype "passive"))
      (node (ref "C17") (pin "1") (pinfunction "1_1") (pintype "passive"))
      (node (ref "D1") (pin "1") (pinfunction "VCC_1") (pintype "power_in"))
      (node (ref "JP3") (pin "3") (pinfunction "3_3") (pintype "passive"))
      (node (ref "Q1") (pin "3") (pinfunction "D_3") (pintype "passive"))
      (node (ref "R21") (pin "2") (pinfunction "2_2") (pintype "passive"))
      (node (ref "R22") (pin "1") (pinfunction "1_1") (pintype "passive"))
      (node (ref "R7") (pin "2") (pinfunction "2_2") (pintype "passive"))
      (node (ref "R8") (pin "2") (pinfunction "2_2") (pintype "passive"))
      (node (ref "SJ7") (pin "1") (pinfunction "1_1") (pintype "passive"))
      (node (ref "TC2") (pin "P$1") (pinfunction "VCC_P$1") (pintype "power_in"))
      (node (ref "U2") (pin "15") (pinfunction "DVDD_15") (pintype "bidirectional"))
      (node (ref "U3") (pin "B4") (pinfunction "3.3V_B4") (pintype "power_in"))
    )
    (net (code "64") (name "VCC") (class "Default")
      (node (ref "C1") (pin "1") (pinfunction "1_1") (pintype "passive"))
      (node (ref "C14") (pin "1") (pinfunction "1_1") (pintype "passive"))
      (node (ref "C15") (pin "1") (pinfunction "1_1") (pintype "passive"))
      (node (ref "C2") (pin "1") (pinfunction "1_1") (pintype "passive"))
      (node (ref "JP6") (pin "3") (pinfunction "3_3") (pintype "passive"))
      (node (ref "Q1") (pin "2") (pinfunction "S_2") (pintype "passive"))
      (node (ref "Q4") (pin "2") (pinfunction "S_2") (pintype "passive"))
      (node (ref "R1") (pin "1") (pinfunction "1_1") (pintype "passive"))
      (node (ref "R2") (pin "2") (pinfunction "2_2") (pintype "passive"))
      (node (ref "R20") (pin "2") (pinfunction "2_2") (pintype "passive"))
      (node (ref "R5") (pin "2") (pinfunction "2_2") (pintype "passive"))
      (node (ref "TC1") (pin "P$1") (pinfunction "VCC_P$1") (pintype "power_in"))
      (node (ref "U1") (pin "2") (pinfunction "3V3_2") (pintype "bidirectional"))
      (node (ref "U5") (pin "4") (pinfunction "VOUT_4") (pintype "power_in"))
    )
    (net (code "65") (name "unconnected-(U1-IO12-Pad14)") (class "Default")
      (node (ref "U1") (pin "14") (pinfunction "IO12_14") (pintype "bidirectional"))
    )
    (net (code "66") (name "unconnected-(U1-IO20-Pad32)") (class "Default")
      (node (ref "U1") (pin "32") (pinfunction "IO20_32") (pintype "bidirectional"))
    )
    (net (code "67") (name "unconnected-(U1-SCK-Pad20)") (class "Default")
      (node (ref "U1") (pin "20") (pinfunction "SCK_20") (pintype "bidirectional"))
    )
    (net (code "68") (name "unconnected-(U1-SCS-Pad19)") (class "Default")
      (node (ref "U1") (pin "19") (pinfunction "SCS_19") (pintype "bidirectional"))
    )
    (net (code "69") (name "unconnected-(U1-SDI-Pad22)") (class "Default")
      (node (ref "U1") (pin "22") (pinfunction "SDI_22") (pintype "bidirectional"))
    )
    (net (code "70") (name "unconnected-(U1-SDO-Pad21)") (class "Default")
      (node (ref "U1") (pin "21") (pinfunction "SDO_21") (pintype "bidirectional"))
    )
    (net (code "71") (name "unconnected-(U1-SHD-Pad17)") (class "Default")
      (node (ref "U1") (pin "17") (pinfunction "SHD_17") (pintype "bidirectional"))
    )
    (net (code "72") (name "unconnected-(U1-SWP-Pad18)") (class "Default")
      (node (ref "U1") (pin "18") (pinfunction "SWP_18") (pintype "bidirectional"))
    )
    (net (code "73") (name "unconnected-(U2-XIN-Pad10)") (class "Default")
      (node (ref "U2") (pin "10") (pinfunction "XIN_10") (pintype "bidirectional"))
    )
    (net (code "74") (name "unconnected-(U2-XOUT-Pad11)") (class "Default")
      (node (ref "U2") (pin "11") (pinfunction "XOUT_11") (pintype "bidirectional"))
    )
    (net (code "75") (name "unconnected-(U3-DIO1-PadB2)") (class "Default")
      (node (ref "U3") (pin "B2") (pinfunction "DIO1_B2") (pintype "bidirectional"))
    )
    (net (code "76") (name "unconnected-(U3-DIO2-PadB1)") (class "Default")
      (node (ref "U3") (pin "B1") (pinfunction "DIO2_B1") (pintype "bidirectional"))
    )
    (net (code "77") (name "unconnected-(U3-DIO3-PadB6)") (class "Default")
      (node (ref "U3") (pin "B6") (pinfunction "DIO3_B6") (pintype "bidirectional"))
    )
    (net (code "78") (name "unconnected-(U3-DIO4-PadB5)") (class "Default")
      (node (ref "U3") (pin "B5") (pinfunction "DIO4_B5") (pintype "bidirectional"))
    )
    (net (code "79") (name "unconnected-(U3-DIO5-PadA7)") (class "Default")
      (node (ref "U3") (pin "A7") (pinfunction "DIO5_A7") (pintype "bidirectional"))
    )
    (net (code "80") (name "unconnected-(U4-XIN-Pad10)") (class "Default")
      (node (ref "U4") (pin "10") (pinfunction "XIN_10") (pintype "bidirectional"))
    )
    (net (code "81") (name "unconnected-(U4-XOUT-Pad11)") (class "Default")
      (node (ref "U4") (pin "11") (pinfunction "XOUT_11") (pintype "bidirectional"))
    )
  )
)
